# Magnetic_Sensor.net
KiCad netlist of a schematic drawn in Altium Designer
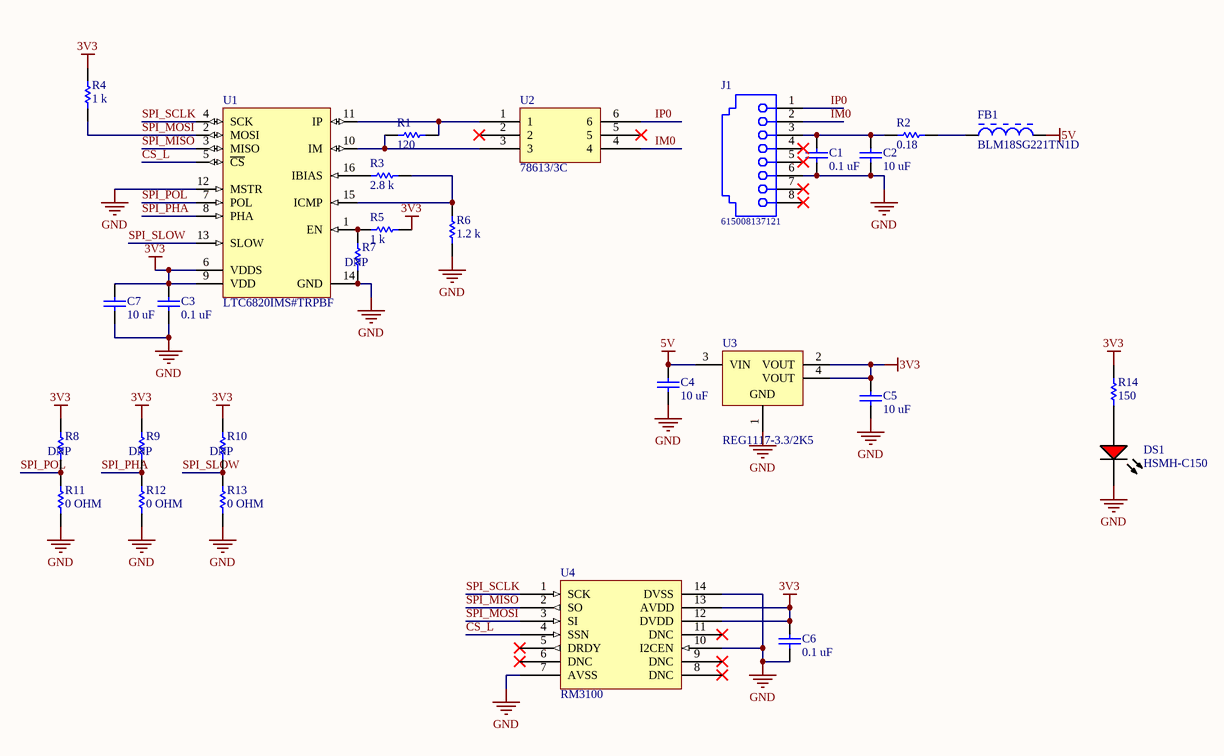
[diagram p0: Magnetic Sensor.SchDoc]

(export (version "E")
  (design (tool "Eeschema 10.0.6"))
  (components
    (comp (ref "C1")
      (value "0.1 uF")
      (footprint "CAPC1608X87X35NL15T15")
      (fields (field (name "PART NUMBER") "C0603X104K5RACTU") (field (name "MANUFACTURER") "Kemet"))
      (libsource (lib "Altium Content Vault") (part "CAP"))
    )
    (comp (ref "C2")
      (value "10 uF")
      (footprint "CAPC1608X90X20ML10")
      (description "Chip Capacitor, 10 uF, +/- 10%, 10 V, -55 to 85 degC, 0603 (1608 Metric), RoHS, Tape and Reel")
      (fields
        (field (name "PCN PART NUMBER") "MLCCPartNumberChange30/Nov/2012")
        (field (name "TOLERANCE") "±10%")
      )
      (libsource (lib "Altium Content Vault") (part "CAP-NP-2"))
    )
    (comp (ref "C3")
      (value "0.1 uF")
      (footprint "CAPC1608X87X35NL15T15")
      (fields (field (name "PART NUMBER") "C0603X104K5RACTU") (field (name "MANUFACTURER") "Kemet"))
      (libsource (lib "Altium Content Vault") (part "CAP"))
    )
    (comp (ref "C4")
      (value "10 uF")
      (footprint "CAPC1608X90X20ML10")
      (description "Chip Capacitor, 10 uF, +/- 10%, 10 V, -55 to 85 degC, 0603 (1608 Metric), RoHS, Tape and Reel")
      (fields
        (field (name "PCN PART NUMBER") "MLCCPartNumberChange30/Nov/2012")
        (field (name "TOLERANCE") "±10%")
      )
      (libsource (lib "Altium Content Vault") (part "CAP-NP-2"))
    )
    (comp (ref "C5")
      (value "10 uF")
      (footprint "CAPC1608X90X20ML10")
      (description "Chip Capacitor, 10 uF, +/- 10%, 10 V, -55 to 85 degC, 0603 (1608 Metric), RoHS, Tape and Reel")
      (fields
        (field (name "PCN PART NUMBER") "MLCCPartNumberChange30/Nov/2012")
        (field (name "TOLERANCE") "±10%")
      )
      (libsource (lib "Altium Content Vault") (part "CAP-NP-2"))
    )
    (comp (ref "C6")
      (value "0.1 uF")
      (footprint "CAPC1608X87X35NL15T15")
      (fields (field (name "PART NUMBER") "C0603X104K5RACTU") (field (name "MANUFACTURER") "Kemet"))
      (libsource (lib "Altium Content Vault") (part "CAP"))
    )
    (comp (ref "C7")
      (value "10 uF")
      (footprint "CAPC1608X90X20ML10")
      (description "Chip Capacitor, 10 uF, +/- 10%, 10 V, -55 to 85 degC, 0603 (1608 Metric), RoHS, Tape and Reel")
      (fields
        (field (name "PCN PART NUMBER") "MLCCPartNumberChange30/Nov/2012")
        (field (name "TOLERANCE") "±10%")
      )
      (libsource (lib "Altium Content Vault") (part "CAP-NP-2"))
    )
    (comp (ref "DS1")
      (value "HSMH-C150")
      (footprint "AVAG-HSMX-C150_V")
      (description "LED Uni-Color Red, 65 mW, 25 mA, -40 to 85 degC, 2-Pin SMD, RoHS, Tape and Reel")
      (fields (field (name "MANUFACTURER") "Avago"))
      (libsource (lib "Altium Content Vault") (part "LED-RED-AK-2"))
    )
    (comp (ref "FB1")
      (value "BLM18SG221TN1D")
      (footprint "MURA-BLM18SG-B25-CHIP-2_V1")
      (fields (field (name "MANUFACTURER") "Murata"))
      (libsource (lib "Altium Content Vault") (part "MURA-FB-2"))
    )
    (comp (ref "J1")
      (value "615008137121")
      (footprint "615008137121")
      (description "Modular Jack WR-MJ, Tab Down, Plastic, Horizontal Entry, THT, 8P8C")
      (fields (field (name "MANUFACTURER") "Wurth Elektronik") (field (name "PUBLISHER") "WurthElektronik"))
      (libsource (lib "Altium Content Vault") (part "WE-CN-1P-F-J8"))
    )
    (comp (ref "R1")
      (value "120")
      (footprint "RESC1609X55X30ML15T15")
      (description "Chip Resistor, 120 Ohm, +/- 1%, 0.1 W, -55 to 155 degC, 0603 (1608 Metric), RoHS, Tape and Reel")
      (fields (field (name "TOLERANCE") "1%") (field (name "MANUFACTURER") "Panasonic"))
      (libsource (lib "Altium Content Vault") (part "RES-2"))
    )
    (comp (ref "R2")
      (value "0.18")
      (footprint "RESC1608X55X30LL15T15")
      (fields (field (name "PART NUMBER") "ERJ-3RSFR18V") (field (name "MANUFACTURER") "Panasonic"))
      (libsource (lib "Altium Content Vault") (part "RES"))
    )
    (comp (ref "R3")
      (value "2.8 k")
      (footprint "RESC0603(1608)_L")
      (description "2K8 0.1W 1% 0603 (1608 Metric)  SMD")
      (fields (field (name "TOLERANCE") "1 %") (field (name "POWER") "0.1 W"))
      (libsource (lib "Altium Content Vault") (part "RES"))
    )
    (comp (ref "R4")
      (value "1 k")
      (footprint "RESC1609X55X30ML10T20")
      (fields (field (name "MANUFACTURER") "Vishay Dale") (field (name "PART NUMBER") "CRCW06031K00FKEAHP"))
      (libsource (lib "Altium Content Vault") (part "RES"))
    )
    (comp (ref "R5")
      (value "1 k")
      (footprint "RESC1609X55X30ML10T20")
      (fields (field (name "MANUFACTURER") "Vishay Dale") (field (name "PART NUMBER") "CRCW06031K00FKEAHP"))
      (libsource (lib "Altium Content Vault") (part "RES"))
    )
    (comp (ref "R6")
      (value "1.2 k")
      (footprint "RESC1608X55X25ML10T15")
      (fields (field (name "PART NUMBER") "AC0603FR-071K2L") (field (name "MANUFACTURER") "Yageo"))
      (libsource (lib "Altium Content Vault") (part "RES"))
    )
    (comp (ref "R7")
      (value "DNP")
      (footprint "RESC1608X55X25ML10T15")
      (description "Chip Resistor, 0 Ohm, +/- 5%, 0.1 W, -55 to 155 degC, 0603 (1608 Metric), RoHS, Tape and Reel")
      (fields (field (name "TOLERANCE") "5%") (field (name "MANUFACTURER") "Yageo"))
      (libsource (lib "Altium Content Vault") (part "RES-2"))
    )
    (comp (ref "R8")
      (value "DNP")
      (footprint "RESC1608X55X25ML10T15")
      (description "Chip Resistor, 0 Ohm, +/- 5%, 0.1 W, -55 to 155 degC, 0603 (1608 Metric), RoHS, Tape and Reel")
      (fields (field (name "TOLERANCE") "5%") (field (name "MANUFACTURER") "Yageo"))
      (libsource (lib "Altium Content Vault") (part "RES-2"))
    )
    (comp (ref "R9")
      (value "DNP")
      (footprint "RESC1608X55X25ML10T15")
      (description "Chip Resistor, 0 Ohm, +/- 5%, 0.1 W, -55 to 155 degC, 0603 (1608 Metric), RoHS, Tape and Reel")
      (fields (field (name "TOLERANCE") "5%") (field (name "MANUFACTURER") "Yageo"))
      (libsource (lib "Altium Content Vault") (part "RES-2"))
    )
    (comp (ref "R10")
      (value "DNP")
      (footprint "RESC1608X55X25ML10T15")
      (description "Chip Resistor, 0 Ohm, +/- 5%, 0.1 W, -55 to 155 degC, 0603 (1608 Metric), RoHS, Tape and Reel")
      (fields (field (name "TOLERANCE") "5%") (field (name "MANUFACTURER") "Yageo"))
      (libsource (lib "Altium Content Vault") (part "RES-2"))
    )
    (comp (ref "R11")
      (value "0 OHM")
      (footprint "RESC1608X55X25ML10T15")
      (description "Chip Resistor, 0 Ohm, +/- 5%, 0.1 W, -55 to 155 degC, 0603 (1608 Metric), RoHS, Tape and Reel")
      (fields (field (name "TOLERANCE") "5%") (field (name "MANUFACTURER") "Yageo"))
      (libsource (lib "Altium Content Vault") (part "RES-2"))
    )
    (comp (ref "R12")
      (value "0 OHM")
      (footprint "RESC1608X55X25ML10T15")
      (description "Chip Resistor, 0 Ohm, +/- 5%, 0.1 W, -55 to 155 degC, 0603 (1608 Metric), RoHS, Tape and Reel")
      (fields (field (name "TOLERANCE") "5%") (field (name "MANUFACTURER") "Yageo"))
      (libsource (lib "Altium Content Vault") (part "RES-2"))
    )
    (comp (ref "R13")
      (value "0 OHM")
      (footprint "RESC1608X55X25ML10T15")
      (description "Chip Resistor, 0 Ohm, +/- 5%, 0.1 W, -55 to 155 degC, 0603 (1608 Metric), RoHS, Tape and Reel")
      (fields (field (name "TOLERANCE") "5%") (field (name "MANUFACTURER") "Yageo"))
      (libsource (lib "Altium Content Vault") (part "RES-2"))
    )
    (comp (ref "R14")
      (value "150")
      (footprint "RESC1608X55X30NL15T15")
      (fields (field (name "PART NUMBER") "ERJ-3EKF1500V") (field (name "MANUFACTURER") "Panasonic"))
      (libsource (lib "Altium Content Vault") (part "RES"))
    )
    (comp (ref "U1")
      (value "LTC6820IMS#TRPBF")
      (footprint "LT-MS-16_N")
      (fields (field (name "MANUFACTURER") "Linear Technology"))
      (libsource (lib "Altium Content Vault") (part "LT-LTC6820-MS-16"))
    )
    (comp (ref "U2")
      (value "78613/3C")
      (footprint "DIP6-400")
      (libsource (lib "myComponents") (part "78613/3C"))
    )
    (comp (ref "U3")
      (value "REG1117-3.3/2K5")
      (footprint "DCY0004A_M")
      (fields (field (name "MANUFACTURER") "Texas Instruments"))
      (libsource (lib "Altium Content Vault") (part "TI-REG1117-XXXX"))
    )
    (comp (ref "U4")
      (value "RM3100")
      (footprint "DIP14-900")
      (libsource (lib "myComponents") (part "RM3100"))
    )
  )
  (nets
    (net (code "1") (name "/CS_L") (class "Default")
      (node (ref "U1") (pin "5") (pinfunction "~{CS}_5") (pintype "bidirectional"))
      (node (ref "U4") (pin "4") (pinfunction "SSN_4") (pintype "input"))
    )
    (net (code "2") (name "/IM0") (class "Default")
      (node (ref "J1") (pin "2") (pinfunction "2_2") (pintype "passive"))
      (node (ref "U2") (pin "4") (pinfunction "4_4") (pintype "passive"))
    )
    (net (code "3") (name "/IP0") (class "Default")
      (node (ref "J1") (pin "1") (pinfunction "1_1") (pintype "passive"))
      (node (ref "U2") (pin "6") (pinfunction "6_6") (pintype "passive"))
    )
    (net (code "4") (name "/SPI_MISO") (class "Default")
      (node (ref "U1") (pin "3") (pinfunction "MISO_3") (pintype "bidirectional"))
      (node (ref "U4") (pin "2") (pinfunction "SO_2") (pintype "output"))
    )
    (net (code "5") (name "/SPI_MOSI") (class "Default")
      (node (ref "R4") (pin "1") (pinfunction "1_1") (pintype "passive"))
      (node (ref "U1") (pin "2") (pinfunction "MOSI_2") (pintype "bidirectional"))
      (node (ref "U4") (pin "3") (pinfunction "SI_3") (pintype "input"))
    )
    (net (code "6") (name "/SPI_PHA") (class "Default")
      (node (ref "R12") (pin "2") (pinfunction "2_2") (pintype "passive"))
      (node (ref "R9") (pin "1") (pinfunction "1_1") (pintype "passive"))
      (node (ref "U1") (pin "8") (pinfunction "PHA_8") (pintype "input"))
    )
    (net (code "7") (name "/SPI_POL") (class "Default")
      (node (ref "R11") (pin "2") (pinfunction "2_2") (pintype "passive"))
      (node (ref "R8") (pin "1") (pinfunction "1_1") (pintype "passive"))
      (node (ref "U1") (pin "7") (pinfunction "POL_7") (pintype "input"))
    )
    (net (code "8") (name "/SPI_SCLK") (class "Default")
      (node (ref "U1") (pin "4") (pinfunction "SCK_4") (pintype "bidirectional"))
      (node (ref "U4") (pin "1") (pinfunction "SCK_1") (pintype "input"))
    )
    (net (code "9") (name "/SPI_SLOW") (class "Default")
      (node (ref "R10") (pin "1") (pinfunction "1_1") (pintype "passive"))
      (node (ref "R13") (pin "2") (pinfunction "2_2") (pintype "passive"))
      (node (ref "U1") (pin "13") (pinfunction "SLOW_13") (pintype "input"))
    )
    (net (code "10") (name "3V3") (class "Default")
      (node (ref "C3") (pin "2") (pinfunction "2_2") (pintype "passive"))
      (node (ref "C5") (pin "2") (pinfunction "2_2") (pintype "passive"))
      (node (ref "C6") (pin "2") (pinfunction "2_2") (pintype "passive"))
      (node (ref "C7") (pin "2") (pinfunction "2_2") (pintype "passive"))
      (node (ref "R10") (pin "2") (pinfunction "2_2") (pintype "passive"))
      (node (ref "R14") (pin "2") (pinfunction "2_2") (pintype "passive"))
      (node (ref "R4") (pin "2") (pinfunction "2_2") (pintype "passive"))
      (node (ref "R5") (pin "2") (pinfunction "2_2") (pintype "passive"))
      (node (ref "R8") (pin "2") (pinfunction "2_2") (pintype "passive"))
      (node (ref "R9") (pin "2") (pinfunction "2_2") (pintype "passive"))
      (node (ref "U1") (pin "6") (pinfunction "VDDS_6") (pintype "power_in"))
      (node (ref "U1") (pin "9") (pinfunction "VDD_9") (pintype "power_in"))
      (node (ref "U3") (pin "2") (pinfunction "VOUT_2") (pintype "power_in"))
      (node (ref "U3") (pin "4") (pinfunction "VOUT_4") (pintype "power_in"))
      (node (ref "U4") (pin "12") (pinfunction "DVDD_12") (pintype "power_in"))
      (node (ref "U4") (pin "13") (pinfunction "AVDD_13") (pintype "power_in"))
    )
    (net (code "11") (name "5V") (class "Default")
      (node (ref "C4") (pin "2") (pinfunction "2_2") (pintype "passive"))
      (node (ref "FB1") (pin "2") (pinfunction "2_2") (pintype "passive"))
      (node (ref "U3") (pin "3") (pinfunction "VIN_3") (pintype "power_in"))
    )
    (net (code "12") (name "GND") (class "Default")
      (node (ref "C1") (pin "1") (pinfunction "1_1") (pintype "passive"))
      (node (ref "C2") (pin "1") (pinfunction "1_1") (pintype "passive"))
      (node (ref "C3") (pin "1") (pinfunction "1_1") (pintype "passive"))
      (node (ref "C4") (pin "1") (pinfunction "1_1") (pintype "passive"))
      (node (ref "C5") (pin "1") (pinfunction "1_1") (pintype "passive"))
      (node (ref "C6") (pin "1") (pinfunction "1_1") (pintype "passive"))
      (node (ref "C7") (pin "1") (pinfunction "1_1") (pintype "passive"))
      (node (ref "DS1") (pin "2") (pinfunction "K_2") (pintype "passive"))
      (node (ref "J1") (pin "6") (pinfunction "6_6") (pintype "passive"))
      (node (ref "R11") (pin "1") (pinfunction "1_1") (pintype "passive"))
      (node (ref "R12") (pin "1") (pinfunction "1_1") (pintype "passive"))
      (node (ref "R13") (pin "1") (pinfunction "1_1") (pintype "passive"))
      (node (ref "R6") (pin "1") (pinfunction "1_1") (pintype "passive"))
      (node (ref "R7") (pin "1") (pinfunction "1_1") (pintype "passive"))
      (node (ref "U1") (pin "12") (pinfunction "MSTR_12") (pintype "input"))
      (node (ref "U1") (pin "14") (pinfunction "GND_14") (pintype "power_in"))
      (node (ref "U3") (pin "1") (pinfunction "GND_1") (pintype "power_in"))
      (node (ref "U4") (pin "10") (pinfunction "I2CEN_10") (pintype "input"))
      (node (ref "U4") (pin "14") (pinfunction "DVSS_14") (pintype "power_in"))
      (node (ref "U4") (pin "7") (pinfunction "AVSS_7") (pintype "power_in"))
    )
    (net (code "13") (name "Net-(C1-Pad2)") (class "Default")
      (node (ref "C1") (pin "2") (pinfunction "2_2") (pintype "passive"))
      (node (ref "C2") (pin "2") (pinfunction "2_2") (pintype "passive"))
      (node (ref "J1") (pin "3") (pinfunction "3_3") (pintype "passive"))
      (node (ref "R2") (pin "1") (pinfunction "1_1") (pintype "passive"))
    )
    (net (code "14") (name "Net-(DS1-A)") (class "Default")
      (node (ref "DS1") (pin "1") (pinfunction "A_1") (pintype "passive"))
      (node (ref "R14") (pin "1") (pinfunction "1_1") (pintype "passive"))
    )
    (net (code "15") (name "Net-(FB1-Pad1)") (class "Default")
      (node (ref "FB1") (pin "1") (pinfunction "1_1") (pintype "passive"))
      (node (ref "R2") (pin "2") (pinfunction "2_2") (pintype "passive"))
    )
    (net (code "16") (name "Net-(U1-EN)") (class "Default")
      (node (ref "R5") (pin "1") (pinfunction "1_1") (pintype "passive"))
      (node (ref "R7") (pin "2") (pinfunction "2_2") (pintype "passive"))
      (node (ref "U1") (pin "1") (pinfunction "EN_1") (pintype "input"))
    )
    (net (code "17") (name "Net-(U1-IBIAS)") (class "Default")
      (node (ref "R3") (pin "1") (pinfunction "1_1") (pintype "passive"))
      (node (ref "U1") (pin "16") (pinfunction "IBIAS_16") (pintype "input"))
    )
    (net (code "18") (name "Net-(U1-ICMP)") (class "Default")
      (node (ref "R3") (pin "2") (pinfunction "2_2") (pintype "passive"))
      (node (ref "R6") (pin "2") (pinfunction "2_2") (pintype "passive"))
      (node (ref "U1") (pin "15") (pinfunction "ICMP_15") (pintype "input"))
    )
    (net (code "19") (name "Net-(U1-IM)") (class "Default")
      (node (ref "R1") (pin "1") (pinfunction "1_1") (pintype "passive"))
      (node (ref "U1") (pin "10") (pinfunction "IM_10") (pintype "bidirectional"))
      (node (ref "U2") (pin "3") (pinfunction "3_3") (pintype "passive"))
    )
    (net (code "20") (name "Net-(U1-IP)") (class "Default")
      (node (ref "R1") (pin "2") (pinfunction "2_2") (pintype "passive"))
      (node (ref "U1") (pin "11") (pinfunction "IP_11") (pintype "bidirectional"))
      (node (ref "U2") (pin "1") (pinfunction "1_1") (pintype "passive"))
    )
    (net (code "21") (name "unconnected-(J1-Pad4)") (class "Default")
      (node (ref "J1") (pin "4") (pinfunction "4_4") (pintype "passive+no_connect"))
    )
    (net (code "22") (name "unconnected-(J1-Pad5)") (class "Default")
      (node (ref "J1") (pin "5") (pinfunction "5_5") (pintype "passive+no_connect"))
    )
    (net (code "23") (name "unconnected-(J1-Pad7)") (class "Default")
      (node (ref "J1") (pin "7") (pinfunction "7_7") (pintype "passive+no_connect"))
    )
    (net (code "24") (name "unconnected-(J1-Pad8)") (class "Default")
      (node (ref "J1") (pin "8") (pinfunction "8_8") (pintype "passive+no_connect"))
    )
    (net (code "25") (name "unconnected-(U2-Pad2)") (class "Default")
      (node (ref "U2") (pin "2") (pinfunction "2_2") (pintype "passive+no_connect"))
    )
    (net (code "26") (name "unconnected-(U2-Pad5)") (class "Default")
      (node (ref "U2") (pin "5") (pinfunction "5_5") (pintype "passive+no_connect"))
    )
    (net (code "27") (name "unconnected-(U4-DNC-Pad6)") (class "Default")
      (node (ref "U4") (pin "6") (pinfunction "DNC_6") (pintype "passive+no_connect"))
    )
    (net (code "28") (name "unconnected-(U4-DNC-Pad8)") (class "Default")
      (node (ref "U4") (pin "8") (pinfunction "DNC_8") (pintype "passive+no_connect"))
    )
    (net (code "29") (name "unconnected-(U4-DNC-Pad9)") (class "Default")
      (node (ref "U4") (pin "9") (pinfunction "DNC_9") (pintype "passive+no_connect"))
    )
    (net (code "30") (name "unconnected-(U4-DNC-Pad11)") (class "Default")
      (node (ref "U4") (pin "11") (pinfunction "DNC_11") (pintype "passive+no_connect"))
    )
    (net (code "31") (name "unconnected-(U4-DRDY-Pad5)") (class "Default")
      (node (ref "U4") (pin "5") (pinfunction "DRDY_5") (pintype "output+no_connect"))
    )
  )
)
